# USBMicro_SCH.net
KiCad netlist of a schematic drawn in EasyEDA
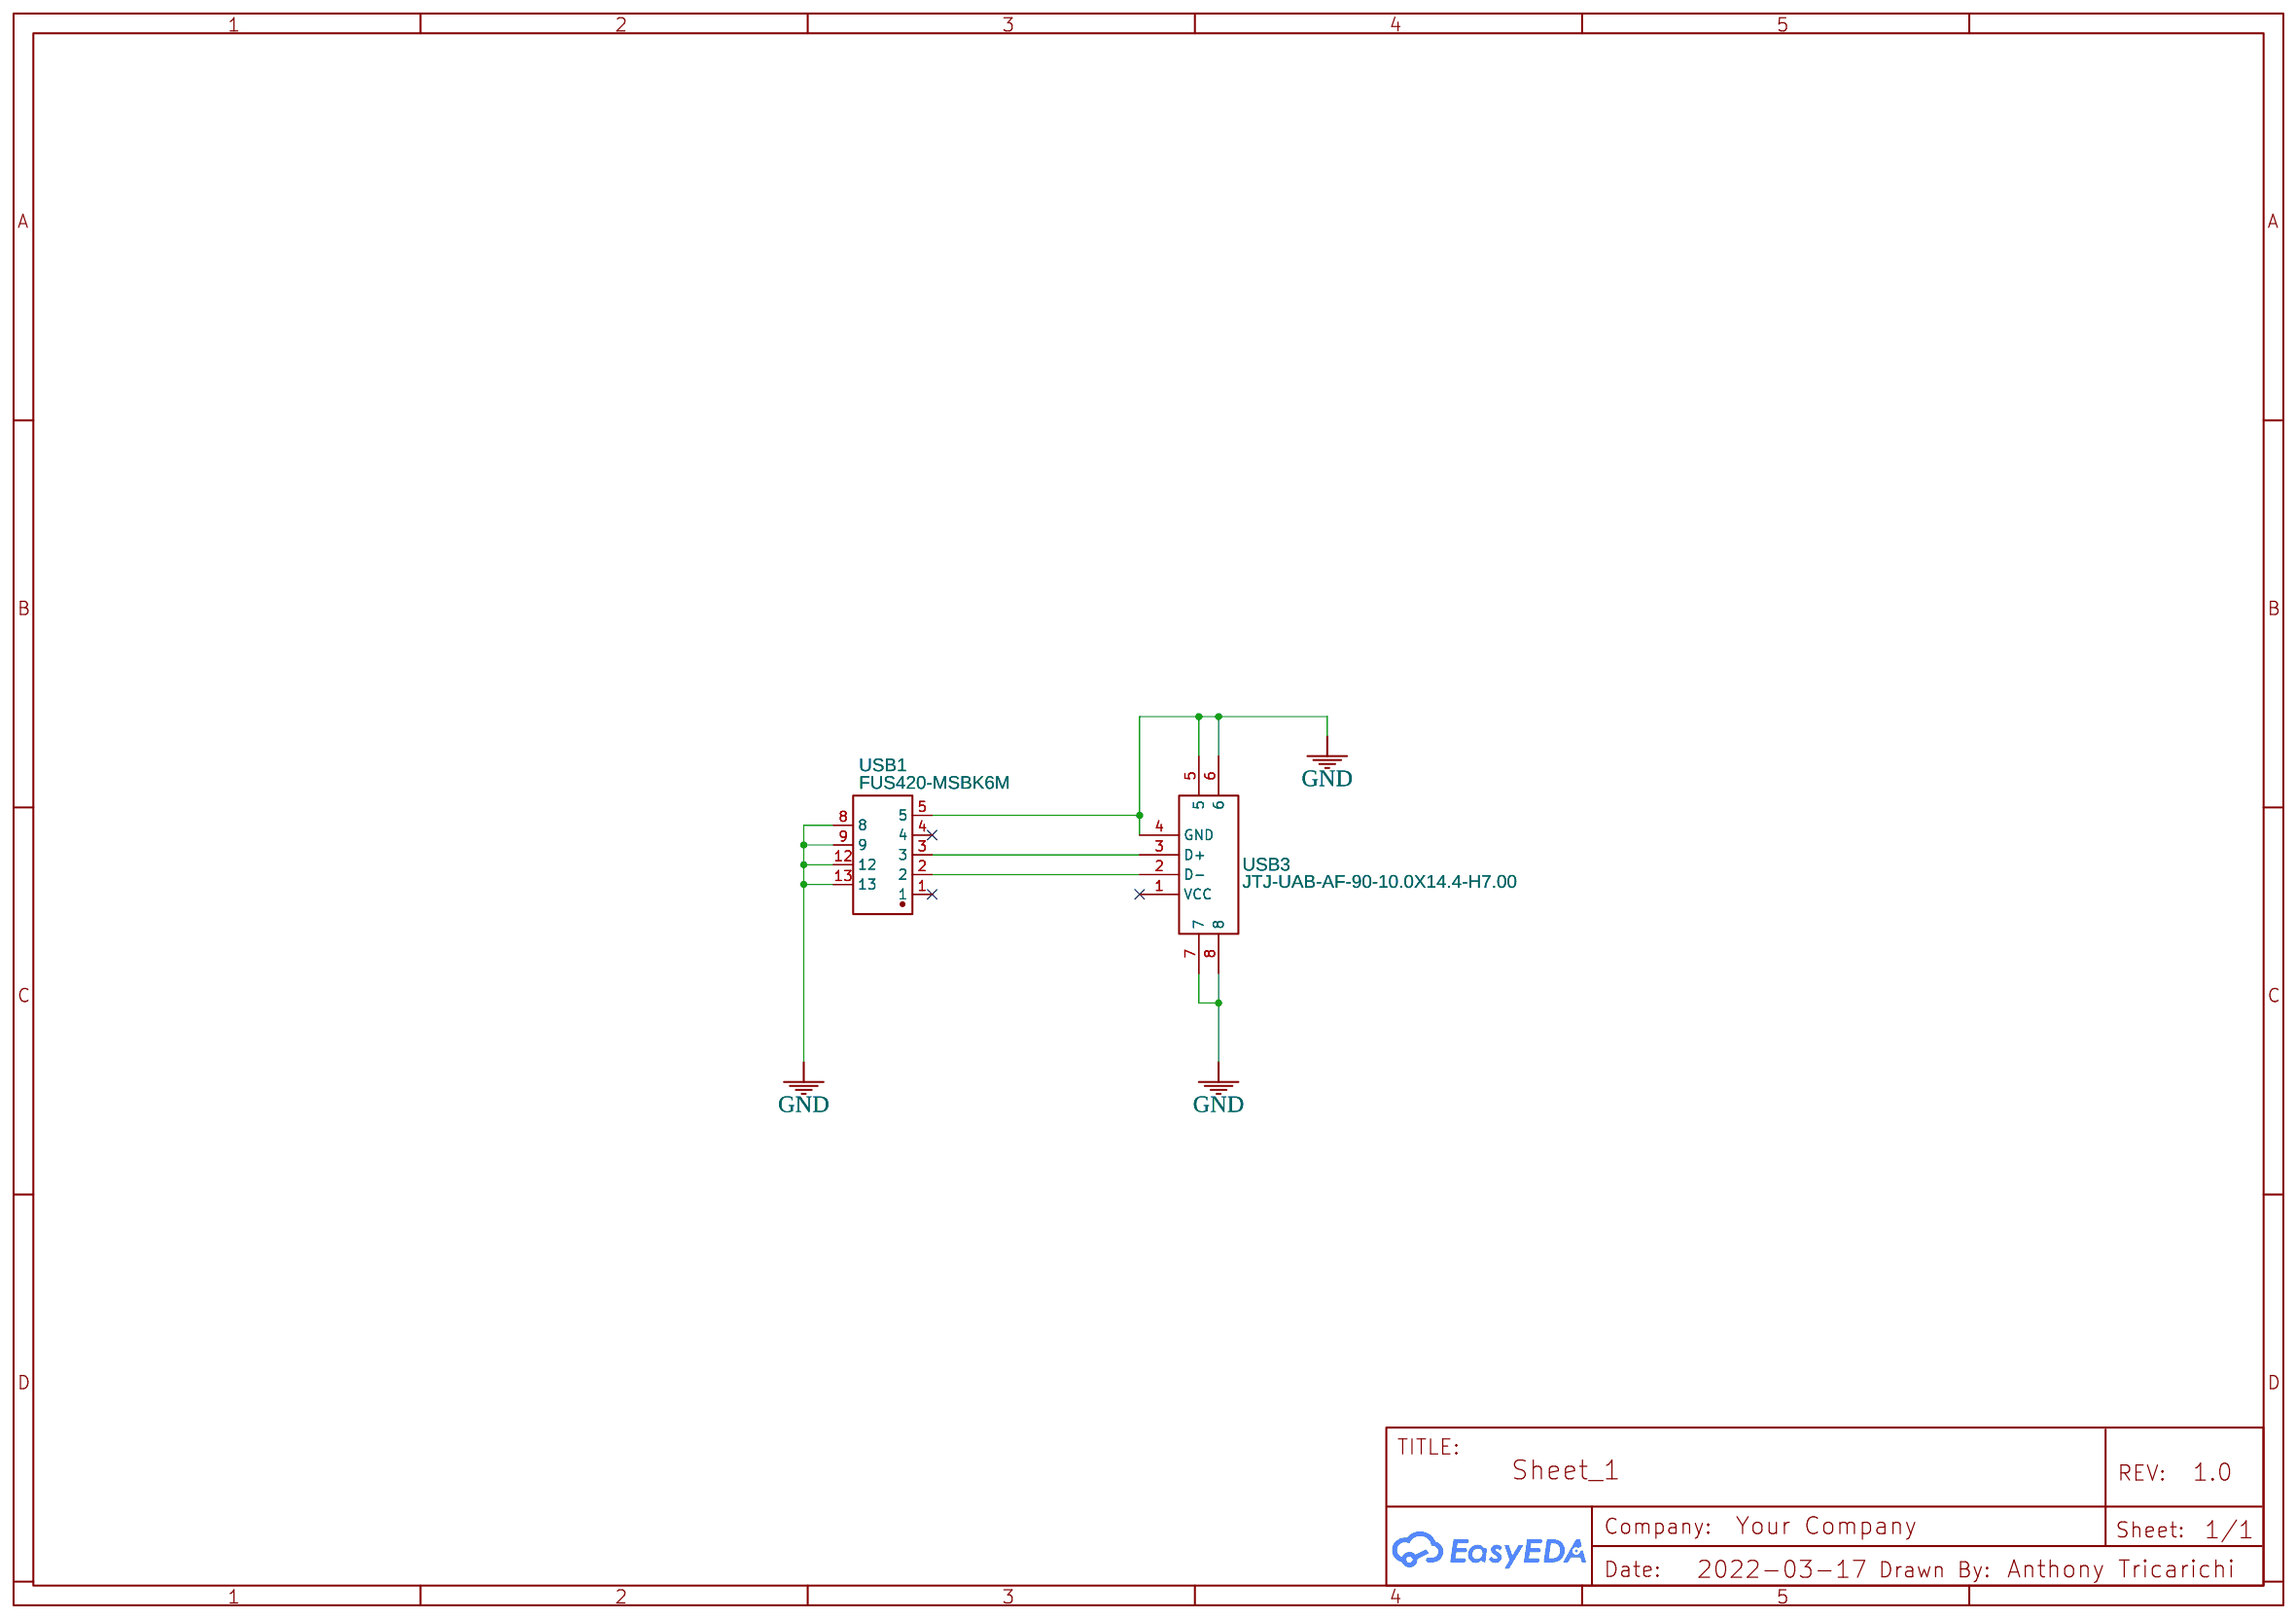
[diagram p0: schematic sheet]

(export (version "E")
  (design (tool "Eeschema 10.0.6"))
  (components
    (comp (ref "USB1")
      (value "FUS420-MSBK6M")
      (fields (field (name "BOM_Supplier Part") "C2833885"))
      (libsource (lib "") (part "FUS420-MSBK6M"))
    )
    (comp (ref "USB3")
      (value "JTJ-UAB-AF-90-10.0X14.4-H7.00")
      (fields (field (name "BOM_Supplier Part") "C42591"))
      (libsource (lib "") (part "JTJ-UAB-AF-90-10.0X14.4-H7.00"))
    )
  )
  (nets
    (net (code "1") (name "GND") (class "Default")
      (node (ref "USB1") (pin "12") (pinfunction "12_12") (pintype "unspecified"))
      (node (ref "USB1") (pin "13") (pinfunction "13_13") (pintype "unspecified"))
      (node (ref "USB1") (pin "5") (pinfunction "5_5") (pintype "unspecified"))
      (node (ref "USB1") (pin "8") (pinfunction "8_8") (pintype "unspecified"))
      (node (ref "USB1") (pin "9") (pinfunction "9_9") (pintype "unspecified"))
      (node (ref "USB3") (pin "4") (pinfunction "GND_4") (pintype "unspecified"))
      (node (ref "USB3") (pin "5") (pinfunction "5_5") (pintype "unspecified"))
      (node (ref "USB3") (pin "6") (pinfunction "6_6") (pintype "unspecified"))
      (node (ref "USB3") (pin "7") (pinfunction "7_7") (pintype "unspecified"))
      (node (ref "USB3") (pin "8") (pinfunction "8_8") (pintype "unspecified"))
    )
    (net (code "2") (name "Net-(USB3-D+)") (class "Default")
      (node (ref "USB1") (pin "3") (pinfunction "3_3") (pintype "unspecified"))
      (node (ref "USB3") (pin "3") (pinfunction "D+_3") (pintype "unspecified"))
    )
    (net (code "3") (name "Net-(USB3-D-)") (class "Default")
      (node (ref "USB1") (pin "2") (pinfunction "2_2") (pintype "unspecified"))
      (node (ref "USB3") (pin "2") (pinfunction "D-_2") (pintype "unspecified"))
    )
    (net (code "4") (name "unconnected-(USB1-Pad1)") (class "Default")
      (node (ref "USB1") (pin "1") (pinfunction "1_1") (pintype "unspecified+no_connect"))
    )
    (net (code "5") (name "unconnected-(USB1-Pad4)") (class "Default")
      (node (ref "USB1") (pin "4") (pinfunction "4_4") (pintype "unspecified+no_connect"))
    )
    (net (code "6") (name "unconnected-(USB3-VCC-Pad1)") (class "Default")
      (node (ref "USB3") (pin "1") (pinfunction "VCC_1") (pintype "unspecified+no_connect"))
    )
  )
)
